# Train_Servo_Mark_II.net
KiCad netlist of a schematic drawn in EAGLE
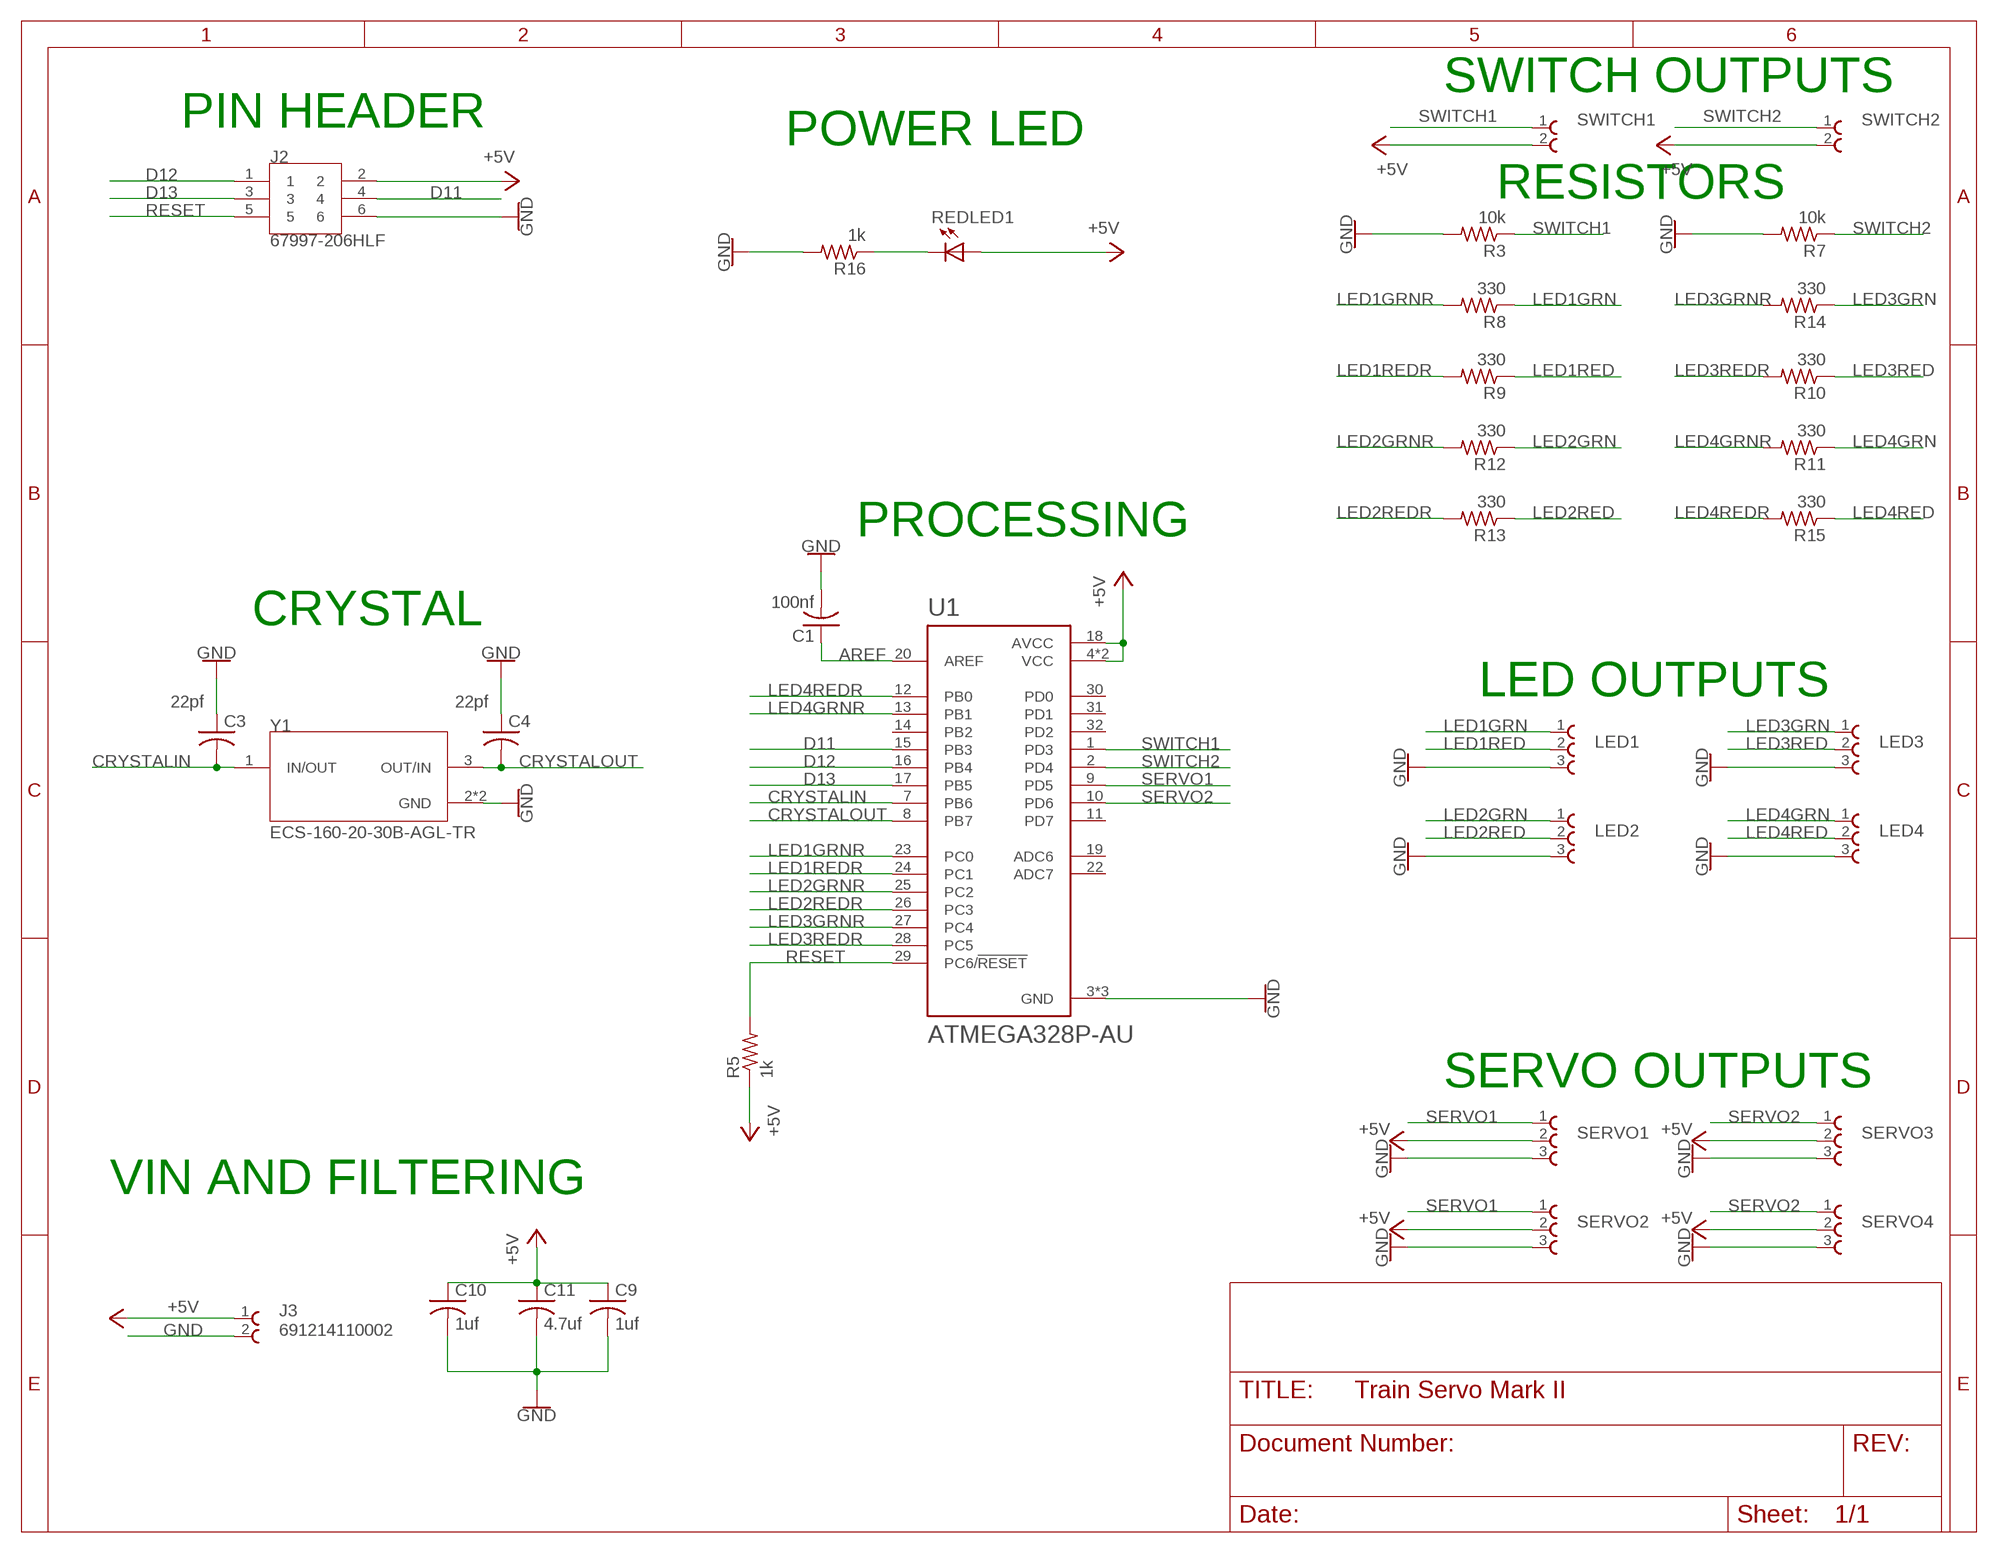
[diagram p0: schematic, sheet 1]

(export (version "E")
  (design (tool "Eeschema 10.0.6"))
  (components
    (comp (ref "C1")
      (value "100nf")
      (footprint "eagle-import:C0805")
      (libsource (lib "eagle-import") (part "C-USC0805"))
    )
    (comp (ref "C3")
      (value "22pf")
      (footprint "eagle-import:C0805")
      (libsource (lib "eagle-import") (part "C-USC0805"))
    )
    (comp (ref "C4")
      (value "22pf")
      (footprint "eagle-import:C0805")
      (libsource (lib "eagle-import") (part "C-USC0805"))
    )
    (comp (ref "C9")
      (value "1uf")
      (footprint "eagle-import:C0805")
      (libsource (lib "eagle-import") (part "C-USC0805"))
    )
    (comp (ref "C10")
      (value "1uf")
      (footprint "eagle-import:C0805")
      (libsource (lib "eagle-import") (part "C-USC0805"))
    )
    (comp (ref "C11")
      (value "4.7uf")
      (footprint "eagle-import:C1206K")
      (libsource (lib "eagle-import") (part "C-USC1206K"))
    )
    (comp (ref "J2")
      (value "67997-206HLF")
      (footprint "eagle-import:FRAMATOME_67997-206HLF")
      (fields (field (name "MF") "Amphenol ICC"))
      (libsource (lib "eagle-import") (part "67997-206HLF"))
    )
    (comp (ref "J3")
      (value "691214110002")
      (footprint "eagle-import:691214110002")
      (fields (field (name "MF") "Wurth Electronics"))
      (libsource (lib "eagle-import") (part "691214110002"))
    )
    (comp (ref "LED1")
      (value "691214110003")
      (footprint "eagle-import:691214110003")
      (fields (field (name "MF") "Wurth Electronics"))
      (libsource (lib "eagle-import") (part "691214110003"))
    )
    (comp (ref "LED2")
      (value "691214110003")
      (footprint "eagle-import:691214110003")
      (fields (field (name "MF") "Wurth Electronics"))
      (libsource (lib "eagle-import") (part "691214110003"))
    )
    (comp (ref "LED3")
      (value "691214110003")
      (footprint "eagle-import:691214110003")
      (fields (field (name "MF") "Wurth Electronics"))
      (libsource (lib "eagle-import") (part "691214110003"))
    )
    (comp (ref "LED4")
      (value "691214110003")
      (footprint "eagle-import:691214110003")
      (fields (field (name "MF") "Wurth Electronics"))
      (libsource (lib "eagle-import") (part "691214110003"))
    )
    (comp (ref "R3")
      (value "10k")
      (footprint "eagle-import:M0805")
      (libsource (lib "eagle-import") (part "R-US_M0805"))
    )
    (comp (ref "R5")
      (value "1k")
      (footprint "eagle-import:M0805")
      (libsource (lib "eagle-import") (part "R-US_M0805"))
    )
    (comp (ref "R7")
      (value "10k")
      (footprint "eagle-import:M0805")
      (libsource (lib "eagle-import") (part "R-US_M0805"))
    )
    (comp (ref "R8")
      (value "330")
      (footprint "eagle-import:M0805")
      (libsource (lib "eagle-import") (part "R-US_M0805"))
    )
    (comp (ref "R9")
      (value "330")
      (footprint "eagle-import:M0805")
      (libsource (lib "eagle-import") (part "R-US_M0805"))
    )
    (comp (ref "R10")
      (value "330")
      (footprint "eagle-import:M0805")
      (libsource (lib "eagle-import") (part "R-US_M0805"))
    )
    (comp (ref "R11")
      (value "330")
      (footprint "eagle-import:M0805")
      (libsource (lib "eagle-import") (part "R-US_M0805"))
    )
    (comp (ref "R12")
      (value "330")
      (footprint "eagle-import:M0805")
      (libsource (lib "eagle-import") (part "R-US_M0805"))
    )
    (comp (ref "R13")
      (value "330")
      (footprint "eagle-import:M0805")
      (libsource (lib "eagle-import") (part "R-US_M0805"))
    )
    (comp (ref "R14")
      (value "330")
      (footprint "eagle-import:M0805")
      (libsource (lib "eagle-import") (part "R-US_M0805"))
    )
    (comp (ref "R15")
      (value "330")
      (footprint "eagle-import:M0805")
      (libsource (lib "eagle-import") (part "R-US_M0805"))
    )
    (comp (ref "R16")
      (value "1k")
      (footprint "eagle-import:M0805")
      (libsource (lib "eagle-import") (part "R-US_M0805"))
    )
    (comp (ref "REDLED1")
      (value "LTST-C171KGKT")
      (footprint "eagle-import:DIOC200X125X110")
      (fields (field (name "MF") "Lite-On Inc."))
      (libsource (lib "eagle-import") (part "LTST-C171KGKT"))
    )
    (comp (ref "SERVO1")
      (value "691214110003")
      (footprint "eagle-import:691214110003")
      (fields (field (name "MF") "Wurth Electronics"))
      (libsource (lib "eagle-import") (part "691214110003"))
    )
    (comp (ref "SERVO2")
      (value "691214110003")
      (footprint "eagle-import:691214110003")
      (fields (field (name "MF") "Wurth Electronics"))
      (libsource (lib "eagle-import") (part "691214110003"))
    )
    (comp (ref "SERVO3")
      (value "691214110003")
      (footprint "eagle-import:691214110003")
      (fields (field (name "MF") "Wurth Electronics"))
      (libsource (lib "eagle-import") (part "691214110003"))
    )
    (comp (ref "SERVO4")
      (value "691214110003")
      (footprint "eagle-import:691214110003")
      (fields (field (name "MF") "Wurth Electronics"))
      (libsource (lib "eagle-import") (part "691214110003"))
    )
    (comp (ref "SWITCH1")
      (value "691214110002")
      (footprint "eagle-import:691214110002")
      (fields (field (name "MF") "Wurth Electronics"))
      (libsource (lib "eagle-import") (part "691214110002"))
    )
    (comp (ref "SWITCH2")
      (value "691214110002")
      (footprint "eagle-import:691214110002")
      (fields (field (name "MF") "Wurth Electronics"))
      (libsource (lib "eagle-import") (part "691214110002"))
    )
    (comp (ref "U1")
      (value "ATMEGA328P-AU")
      (footprint "eagle-import:QFP80P900X900X120-32N")
      (fields (field (name "MF") "Microchip"))
      (libsource (lib "eagle-import") (part "ATMEGA328P-AU"))
    )
    (comp (ref "Y1")
      (value "ECS-160-20-30B-AGL-TR")
      (footprint "eagle-import:XTAL_ECS-160-20-30B-AGL-TR")
      (fields (field (name "MF") "ECS Inc."))
      (libsource (lib "eagle-import") (part "ECS-160-20-30B-AGL-TR"))
    )
  )
  (nets
    (net (code "1") (name "+5V") (class "Default")
      (node (ref "C10") (pin "1") (pinfunction "1_1") (pintype "passive"))
      (node (ref "C11") (pin "1") (pinfunction "1_1") (pintype "passive"))
      (node (ref "C9") (pin "1") (pinfunction "1_1") (pintype "passive"))
      (node (ref "J2") (pin "2") (pinfunction "2_2") (pintype "passive"))
      (node (ref "J3") (pin "1") (pinfunction "1_1") (pintype "passive"))
      (node (ref "R5") (pin "1") (pinfunction "1_1") (pintype "passive"))
      (node (ref "REDLED1") (pin "+") (pinfunction "+_+") (pintype "passive"))
      (node (ref "SERVO1") (pin "2") (pinfunction "2_2") (pintype "passive"))
      (node (ref "SERVO2") (pin "2") (pinfunction "2_2") (pintype "passive"))
      (node (ref "SERVO3") (pin "2") (pinfunction "2_2") (pintype "passive"))
      (node (ref "SERVO4") (pin "2") (pinfunction "2_2") (pintype "passive"))
      (node (ref "SWITCH1") (pin "2") (pinfunction "2_2") (pintype "passive"))
      (node (ref "SWITCH2") (pin "2") (pinfunction "2_2") (pintype "passive"))
      (node (ref "U1") (pin "18") (pinfunction "AVCC_18") (pintype "power_in"))
      (node (ref "U1") (pin "4") (pinfunction "VCC_4") (pintype "power_in"))
      (node (ref "U1") (pin "6") (pinfunction "VCC_6") (pintype "power_in"))
    )
    (net (code "2") (name "/AREF") (class "Default")
      (node (ref "C1") (pin "1") (pinfunction "1_1") (pintype "passive"))
      (node (ref "U1") (pin "20") (pinfunction "AREF_20") (pintype "input"))
    )
    (net (code "3") (name "/CRYSTALIN") (class "Default")
      (node (ref "C3") (pin "2") (pinfunction "2_2") (pintype "passive"))
      (node (ref "U1") (pin "7") (pinfunction "PB6_7") (pintype "bidirectional"))
      (node (ref "Y1") (pin "1") (pinfunction "IN/OUT_1") (pintype "bidirectional"))
    )
    (net (code "4") (name "/CRYSTALOUT") (class "Default")
      (node (ref "C4") (pin "2") (pinfunction "2_2") (pintype "passive"))
      (node (ref "U1") (pin "8") (pinfunction "PB7_8") (pintype "bidirectional"))
      (node (ref "Y1") (pin "3") (pinfunction "OUT/IN_3") (pintype "bidirectional"))
    )
    (net (code "5") (name "/D11") (class "Default")
      (node (ref "J2") (pin "4") (pinfunction "4_4") (pintype "passive"))
      (node (ref "U1") (pin "15") (pinfunction "PB3_15") (pintype "bidirectional"))
    )
    (net (code "6") (name "/D12") (class "Default")
      (node (ref "J2") (pin "1") (pinfunction "1_1") (pintype "passive"))
      (node (ref "U1") (pin "16") (pinfunction "PB4_16") (pintype "bidirectional"))
    )
    (net (code "7") (name "/D13") (class "Default")
      (node (ref "J2") (pin "3") (pinfunction "3_3") (pintype "passive"))
      (node (ref "U1") (pin "17") (pinfunction "PB5_17") (pintype "bidirectional"))
    )
    (net (code "8") (name "/LED1GRN") (class "Default")
      (node (ref "LED1") (pin "1") (pinfunction "1_1") (pintype "passive"))
      (node (ref "R8") (pin "1") (pinfunction "1_1") (pintype "passive"))
    )
    (net (code "9") (name "/LED1GRNR") (class "Default")
      (node (ref "R8") (pin "2") (pinfunction "2_2") (pintype "passive"))
      (node (ref "U1") (pin "23") (pinfunction "PC0_23") (pintype "bidirectional"))
    )
    (net (code "10") (name "/LED1RED") (class "Default")
      (node (ref "LED1") (pin "2") (pinfunction "2_2") (pintype "passive"))
      (node (ref "R9") (pin "1") (pinfunction "1_1") (pintype "passive"))
    )
    (net (code "11") (name "/LED1REDR") (class "Default")
      (node (ref "R9") (pin "2") (pinfunction "2_2") (pintype "passive"))
      (node (ref "U1") (pin "24") (pinfunction "PC1_24") (pintype "bidirectional"))
    )
    (net (code "12") (name "/LED2GRN") (class "Default")
      (node (ref "LED2") (pin "1") (pinfunction "1_1") (pintype "passive"))
      (node (ref "R12") (pin "1") (pinfunction "1_1") (pintype "passive"))
    )
    (net (code "13") (name "/LED2GRNR") (class "Default")
      (node (ref "R12") (pin "2") (pinfunction "2_2") (pintype "passive"))
      (node (ref "U1") (pin "25") (pinfunction "PC2_25") (pintype "bidirectional"))
    )
    (net (code "14") (name "/LED2RED") (class "Default")
      (node (ref "LED2") (pin "2") (pinfunction "2_2") (pintype "passive"))
      (node (ref "R13") (pin "1") (pinfunction "1_1") (pintype "passive"))
    )
    (net (code "15") (name "/LED2REDR") (class "Default")
      (node (ref "R13") (pin "2") (pinfunction "2_2") (pintype "passive"))
      (node (ref "U1") (pin "26") (pinfunction "PC3_26") (pintype "bidirectional"))
    )
    (net (code "16") (name "/LED3GRN") (class "Default")
      (node (ref "LED3") (pin "1") (pinfunction "1_1") (pintype "passive"))
      (node (ref "R14") (pin "1") (pinfunction "1_1") (pintype "passive"))
    )
    (net (code "17") (name "/LED3GRNR") (class "Default")
      (node (ref "R14") (pin "2") (pinfunction "2_2") (pintype "passive"))
      (node (ref "U1") (pin "27") (pinfunction "PC4_27") (pintype "bidirectional"))
    )
    (net (code "18") (name "/LED3RED") (class "Default")
      (node (ref "LED3") (pin "2") (pinfunction "2_2") (pintype "passive"))
      (node (ref "R10") (pin "1") (pinfunction "1_1") (pintype "passive"))
    )
    (net (code "19") (name "/LED3REDR") (class "Default")
      (node (ref "R10") (pin "2") (pinfunction "2_2") (pintype "passive"))
      (node (ref "U1") (pin "28") (pinfunction "PC5_28") (pintype "bidirectional"))
    )
    (net (code "20") (name "/LED4GRN") (class "Default")
      (node (ref "LED4") (pin "1") (pinfunction "1_1") (pintype "passive"))
      (node (ref "R11") (pin "1") (pinfunction "1_1") (pintype "passive"))
    )
    (net (code "21") (name "/LED4GRNR") (class "Default")
      (node (ref "R11") (pin "2") (pinfunction "2_2") (pintype "passive"))
      (node (ref "U1") (pin "13") (pinfunction "PB1_13") (pintype "bidirectional"))
    )
    (net (code "22") (name "/LED4RED") (class "Default")
      (node (ref "LED4") (pin "2") (pinfunction "2_2") (pintype "passive"))
      (node (ref "R15") (pin "1") (pinfunction "1_1") (pintype "passive"))
    )
    (net (code "23") (name "/LED4REDR") (class "Default")
      (node (ref "R15") (pin "2") (pinfunction "2_2") (pintype "passive"))
      (node (ref "U1") (pin "12") (pinfunction "PB0_12") (pintype "bidirectional"))
    )
    (net (code "24") (name "/RESET") (class "Default")
      (node (ref "J2") (pin "5") (pinfunction "5_5") (pintype "passive"))
      (node (ref "R5") (pin "2") (pinfunction "2_2") (pintype "passive"))
      (node (ref "U1") (pin "29") (pinfunction "PC6/~{RESET}_29") (pintype "bidirectional"))
    )
    (net (code "25") (name "/SERVO1") (class "Default")
      (node (ref "SERVO1") (pin "1") (pinfunction "1_1") (pintype "passive"))
      (node (ref "SERVO2") (pin "1") (pinfunction "1_1") (pintype "passive"))
      (node (ref "U1") (pin "9") (pinfunction "PD5_9") (pintype "bidirectional"))
    )
    (net (code "26") (name "/SERVO2") (class "Default")
      (node (ref "SERVO3") (pin "1") (pinfunction "1_1") (pintype "passive"))
      (node (ref "SERVO4") (pin "1") (pinfunction "1_1") (pintype "passive"))
      (node (ref "U1") (pin "10") (pinfunction "PD6_10") (pintype "bidirectional"))
    )
    (net (code "27") (name "/SWITCH1") (class "Default")
      (node (ref "R3") (pin "1") (pinfunction "1_1") (pintype "passive"))
      (node (ref "SWITCH1") (pin "1") (pinfunction "1_1") (pintype "passive"))
      (node (ref "U1") (pin "1") (pinfunction "PD3_1") (pintype "bidirectional"))
    )
    (net (code "28") (name "/SWITCH2") (class "Default")
      (node (ref "R7") (pin "1") (pinfunction "1_1") (pintype "passive"))
      (node (ref "SWITCH2") (pin "1") (pinfunction "1_1") (pintype "passive"))
      (node (ref "U1") (pin "2") (pinfunction "PD4_2") (pintype "bidirectional"))
    )
    (net (code "29") (name "GND") (class "Default")
      (node (ref "C1") (pin "2") (pinfunction "2_2") (pintype "passive"))
      (node (ref "C10") (pin "2") (pinfunction "2_2") (pintype "passive"))
      (node (ref "C11") (pin "2") (pinfunction "2_2") (pintype "passive"))
      (node (ref "C3") (pin "1") (pinfunction "1_1") (pintype "passive"))
      (node (ref "C4") (pin "1") (pinfunction "1_1") (pintype "passive"))
      (node (ref "C9") (pin "2") (pinfunction "2_2") (pintype "passive"))
      (node (ref "J2") (pin "6") (pinfunction "6_6") (pintype "passive"))
      (node (ref "J3") (pin "2") (pinfunction "2_2") (pintype "passive"))
      (node (ref "LED1") (pin "3") (pinfunction "3_3") (pintype "passive"))
      (node (ref "LED2") (pin "3") (pinfunction "3_3") (pintype "passive"))
      (node (ref "LED3") (pin "3") (pinfunction "3_3") (pintype "passive"))
      (node (ref "LED4") (pin "3") (pinfunction "3_3") (pintype "passive"))
      (node (ref "R16") (pin "2") (pinfunction "2_2") (pintype "passive"))
      (node (ref "R3") (pin "2") (pinfunction "2_2") (pintype "passive"))
      (node (ref "R7") (pin "2") (pinfunction "2_2") (pintype "passive"))
      (node (ref "SERVO1") (pin "3") (pinfunction "3_3") (pintype "passive"))
      (node (ref "SERVO2") (pin "3") (pinfunction "3_3") (pintype "passive"))
      (node (ref "SERVO3") (pin "3") (pinfunction "3_3") (pintype "passive"))
      (node (ref "SERVO4") (pin "3") (pinfunction "3_3") (pintype "passive"))
      (node (ref "U1") (pin "21") (pinfunction "GND_21") (pintype "power_in"))
      (node (ref "U1") (pin "3") (pinfunction "GND_3") (pintype "power_in"))
      (node (ref "U1") (pin "5") (pinfunction "GND_5") (pintype "power_in"))
      (node (ref "Y1") (pin "2") (pinfunction "GND_2") (pintype "power_in"))
      (node (ref "Y1") (pin "4") (pinfunction "GND_4") (pintype "power_in"))
    )
    (net (code "30") (name "Net-(R16-Pad1)") (class "Default")
      (node (ref "R16") (pin "1") (pinfunction "1_1") (pintype "passive"))
      (node (ref "REDLED1") (pin "-") (pinfunction "-_-") (pintype "passive"))
    )
    (net (code "31") (name "unconnected-(U1-ADC6-Pad19)") (class "Default")
      (node (ref "U1") (pin "19") (pinfunction "ADC6_19") (pintype "bidirectional"))
    )
    (net (code "32") (name "unconnected-(U1-ADC7-Pad22)") (class "Default")
      (node (ref "U1") (pin "22") (pinfunction "ADC7_22") (pintype "bidirectional"))
    )
    (net (code "33") (name "unconnected-(U1-PB2-Pad14)") (class "Default")
      (node (ref "U1") (pin "14") (pinfunction "PB2_14") (pintype "bidirectional"))
    )
    (net (code "34") (name "unconnected-(U1-PD0-Pad30)") (class "Default")
      (node (ref "U1") (pin "30") (pinfunction "PD0_30") (pintype "bidirectional"))
    )
    (net (code "35") (name "unconnected-(U1-PD1-Pad31)") (class "Default")
      (node (ref "U1") (pin "31") (pinfunction "PD1_31") (pintype "bidirectional"))
    )
    (net (code "36") (name "unconnected-(U1-PD2-Pad32)") (class "Default")
      (node (ref "U1") (pin "32") (pinfunction "PD2_32") (pintype "bidirectional"))
    )
    (net (code "37") (name "unconnected-(U1-PD7-Pad11)") (class "Default")
      (node (ref "U1") (pin "11") (pinfunction "PD7_11") (pintype "bidirectional"))
    )
  )
)
